# fonte_de_tensao.net
KiCad netlist of a schematic drawn in EAGLE
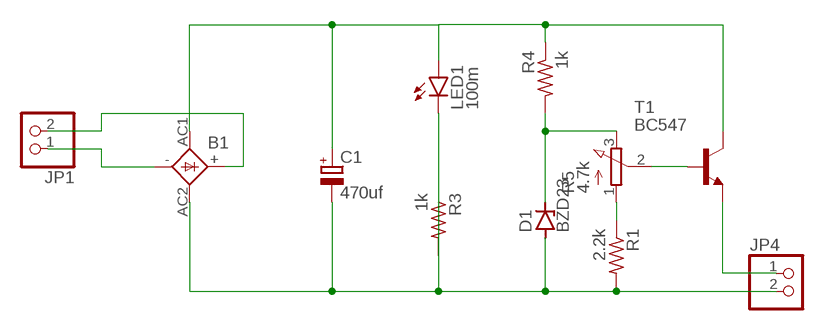
[diagram p0: schematic, sheet 1]

(export (version "E")
  (design (tool "Eeschema 10.0.6"))
  (components
    (comp (ref "B1")
      (value "1KAB")
      (footprint "eagle-import:1KAB")
      (libsource (lib "eagle-import") (part "1KAB"))
    )
    (comp (ref "C1")
      (value "470uf")
      (footprint "eagle-import:E3,5-10")
      (libsource (lib "eagle-import") (part "CPOL-EUE3.5-10"))
    )
    (comp (ref "D1")
      (value "BZD23")
      (footprint "eagle-import:SOD81")
      (libsource (lib "eagle-import") (part "BZD23"))
    )
    (comp (ref "JP1")
      (value "PINHD-1X2")
      (footprint "eagle-import:1X02")
      (libsource (lib "eagle-import") (part "PINHD-1X2"))
    )
    (comp (ref "JP4")
      (value "PINHD-1X2")
      (footprint "eagle-import:1X02")
      (libsource (lib "eagle-import") (part "PINHD-1X2"))
    )
    (comp (ref "LED1")
      (value "100m")
      (footprint "eagle-import:LED5MM")
      (libsource (lib "eagle-import") (part "LED5MM"))
    )
    (comp (ref "R1")
      (value "2.2k")
      (footprint "eagle-import:0309_12")
      (libsource (lib "eagle-import") (part "R-US_0309/12"))
    )
    (comp (ref "R3")
      (value "1k")
      (footprint "eagle-import:0309_12")
      (libsource (lib "eagle-import") (part "R-US_0309/12"))
    )
    (comp (ref "R4")
      (value "1k")
      (footprint "eagle-import:0309_12")
      (libsource (lib "eagle-import") (part "R-US_0309/12"))
    )
    (comp (ref "R5")
      (value "4.7k")
      (footprint "eagle-import:3RP_1610N")
      (libsource (lib "eagle-import") (part "3RP/1610N"))
    )
    (comp (ref "T1")
      (value "BC547")
      (footprint "eagle-import:TO92")
      (libsource (lib "eagle-import") (part "BC547"))
    )
  )
  (nets
    (net (code "1") (name "Net-(B1-Pad+)") (class "Default")
      (node (ref "B1") (pin "+") (pinfunction "+_+") (pintype "passive"))
      (node (ref "JP1") (pin "2") (pinfunction "2_2") (pintype "passive"))
    )
    (net (code "2") (name "Net-(B1-Pad-)") (class "Default")
      (node (ref "B1") (pin "-") (pinfunction "-_-") (pintype "passive"))
      (node (ref "JP1") (pin "1") (pinfunction "1_1") (pintype "passive"))
    )
    (net (code "3") (name "Net-(B1-PadAC2)") (class "Default")
      (node (ref "B1") (pin "AC2") (pinfunction "AC2_AC2") (pintype "passive"))
      (node (ref "C1") (pin "-") (pinfunction "-_-") (pintype "passive"))
      (node (ref "D1") (pin "A") (pinfunction "A_A") (pintype "passive"))
      (node (ref "JP4") (pin "2") (pinfunction "2_2") (pintype "passive"))
      (node (ref "R1") (pin "2") (pinfunction "2_2") (pintype "passive"))
      (node (ref "R3") (pin "1") (pinfunction "1_1") (pintype "passive"))
    )
    (net (code "4") (name "Net-(LED1-C)") (class "Default")
      (node (ref "LED1") (pin "K") (pinfunction "C_K") (pintype "passive"))
      (node (ref "R3") (pin "2") (pinfunction "2_2") (pintype "passive"))
    )
    (net (code "5") (name "Net-(R5-A)") (class "Default")
      (node (ref "R1") (pin "1") (pinfunction "1_1") (pintype "passive"))
      (node (ref "R5") (pin "1") (pinfunction "A_1") (pintype "passive"))
    )
    (net (code "6") (name "Net-(R5-E)") (class "Default")
      (node (ref "D1") (pin "C") (pinfunction "C_C") (pintype "passive"))
      (node (ref "R4") (pin "2") (pinfunction "2_2") (pintype "passive"))
      (node (ref "R5") (pin "3") (pinfunction "E_3") (pintype "passive"))
    )
    (net (code "7") (name "Net-(R5-S)") (class "Default")
      (node (ref "R5") (pin "2") (pinfunction "S_2") (pintype "passive"))
      (node (ref "T1") (pin "2") (pinfunction "B_2") (pintype "passive"))
    )
    (net (code "8") (name "Net-(T1-C)") (class "Default")
      (node (ref "B1") (pin "AC1") (pinfunction "AC1_AC1") (pintype "passive"))
      (node (ref "C1") (pin "+") (pinfunction "+_+") (pintype "passive"))
      (node (ref "LED1") (pin "A") (pinfunction "A_A") (pintype "passive"))
      (node (ref "R4") (pin "1") (pinfunction "1_1") (pintype "passive"))
      (node (ref "T1") (pin "3") (pinfunction "C_3") (pintype "passive"))
    )
    (net (code "9") (name "Net-(T1-E)") (class "Default")
      (node (ref "JP4") (pin "1") (pinfunction "1_1") (pintype "passive"))
      (node (ref "T1") (pin "1") (pinfunction "E_1") (pintype "passive"))
    )
  )
)
